# PC20230001.net
KiCad netlist of a schematic drawn in EasyEDA Pro
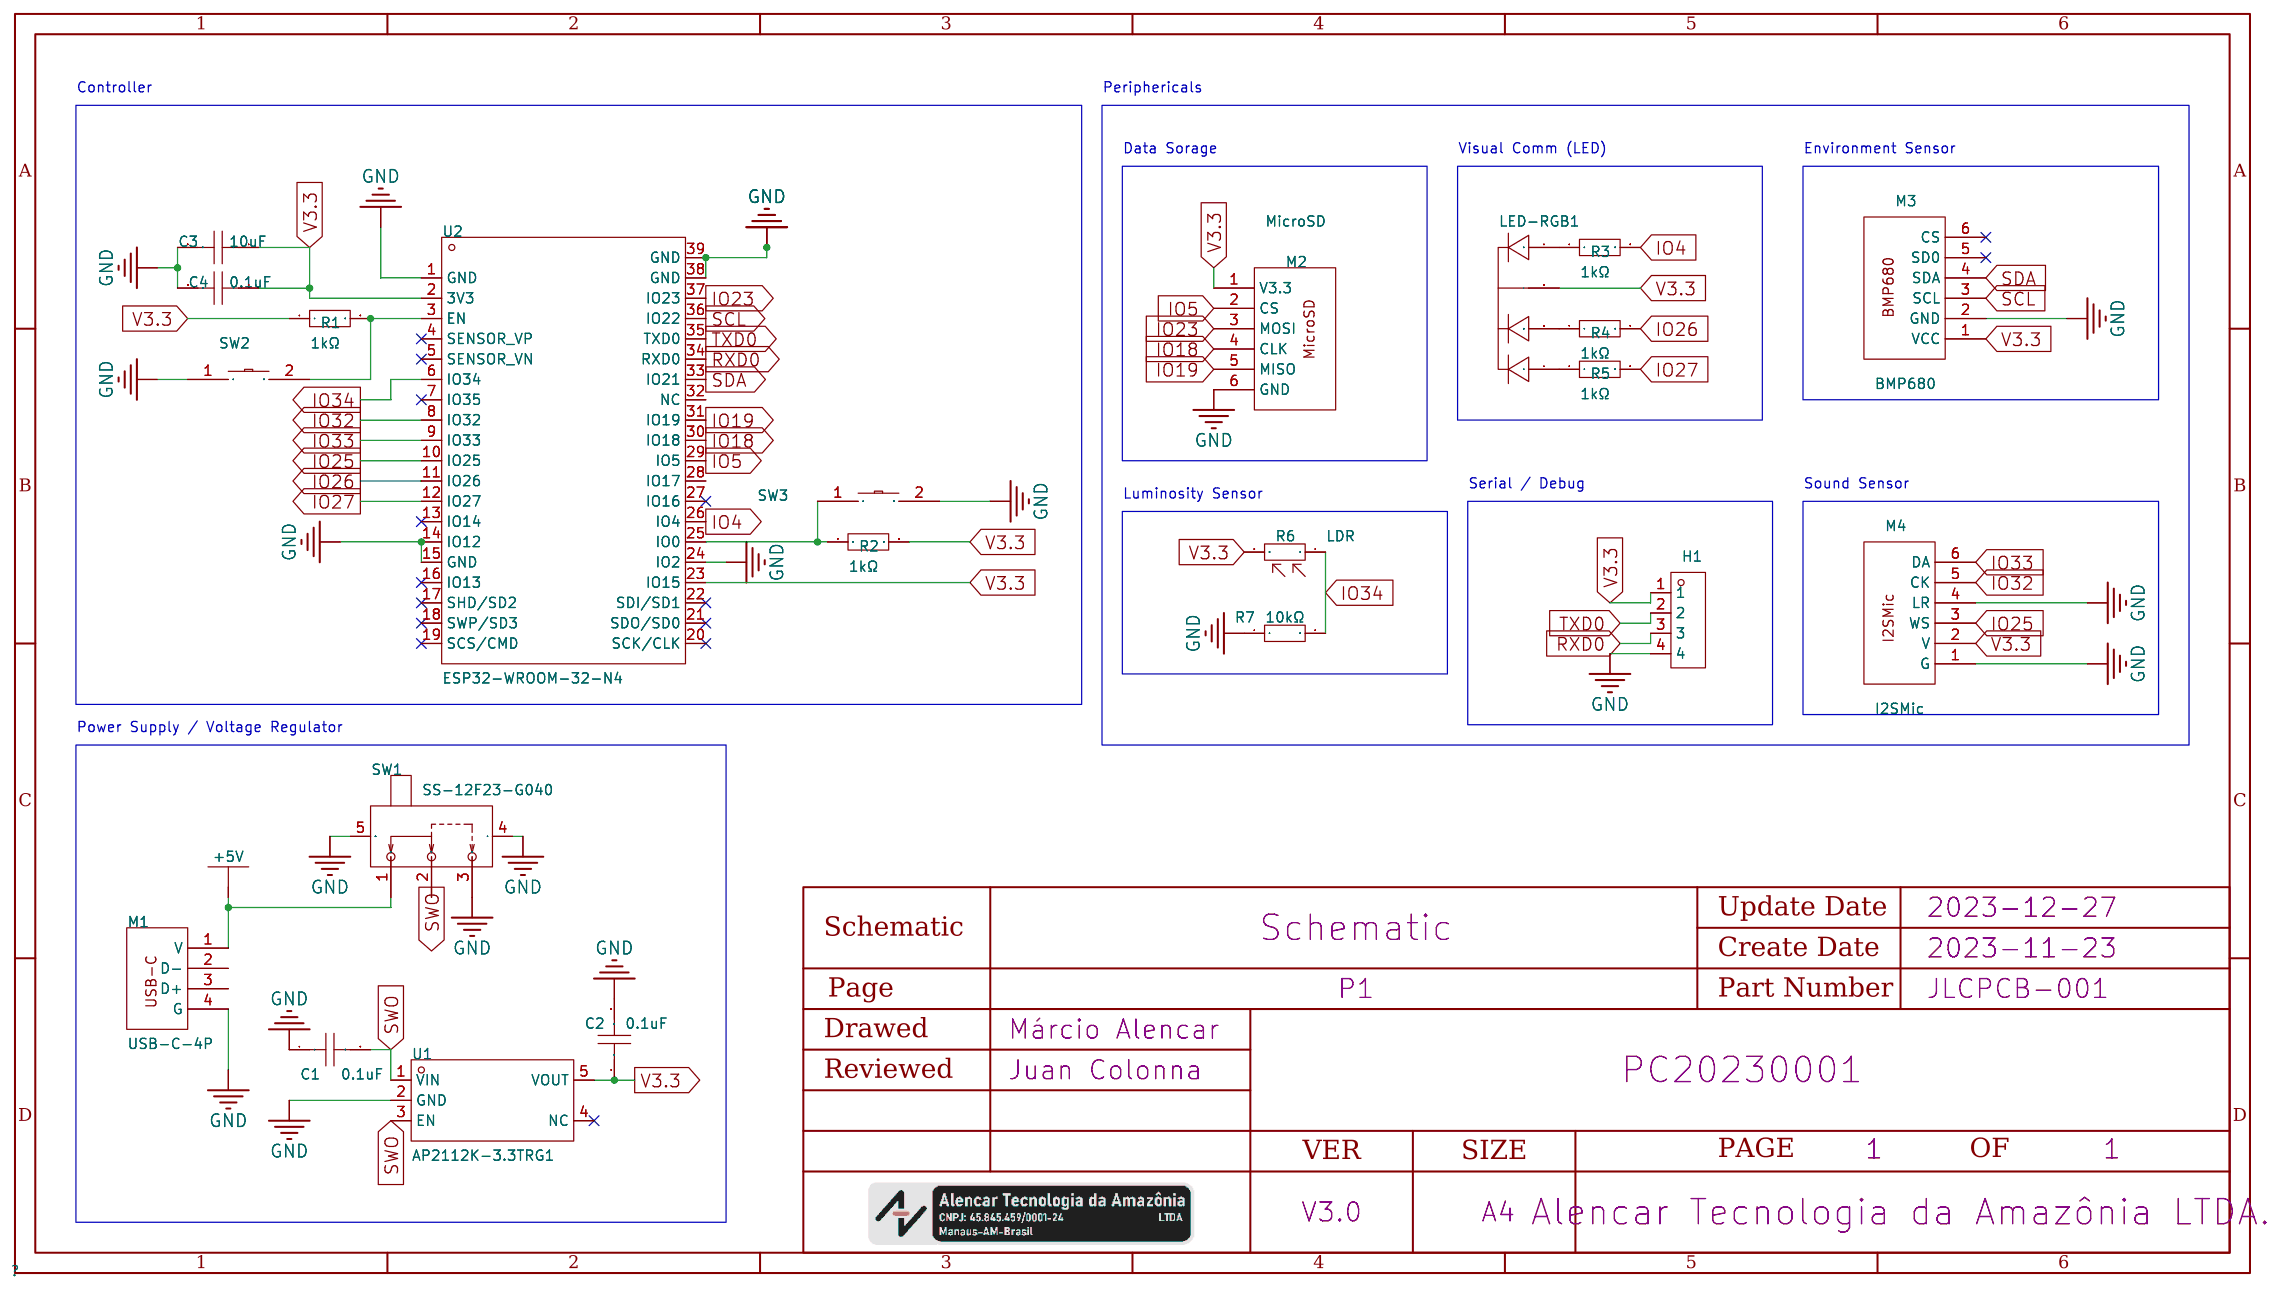
[diagram p0: schematic sheet]

(export (version "E")
  (design (tool "Eeschema 10.0.6"))
  (components
    (comp (ref "C1")
      (value "0.1uF")
      (footprint "easyedapro:C0201")
      (libsource (lib "easyedapro") (part "CAP"))
    )
    (comp (ref "C2")
      (value "0.1uF")
      (footprint "easyedapro:C0201")
      (libsource (lib "easyedapro") (part "CAP"))
    )
    (comp (ref "C3")
      (value "10uF")
      (footprint "easyedapro:C0201")
      (libsource (lib "easyedapro") (part "CAP"))
    )
    (comp (ref "C4")
      (value "0.1uF")
      (footprint "easyedapro:C0201")
      (libsource (lib "easyedapro") (part "CAP"))
    )
    (comp (ref "H1")
      (value "~")
      (footprint "easyedapro:HDR-TH_4P-P2.54-V-F")
      (libsource (lib "easyedapro") (part "2.54-1*4P母"))
    )
    (comp (ref "LED-RGB1")
      (value "LED-RGB 共阴 插件 直径5mm")
      (footprint "easyedapro:LED-TH_4P-BD5.8-P1.30")
      (libsource (lib "easyedapro") (part "LED-RGB 共阴 插件 直径5MM"))
    )
    (comp (ref "M1")
      (value "USB-C-4P")
      (footprint "easyedapro:USB-C-4P_SMD")
      (libsource (lib "easyedapro") (part "USB-C"))
    )
    (comp (ref "M2")
      (value "MicroSD")
      (footprint "easyedapro:MicroSD_SMD")
      (libsource (lib "easyedapro") (part "MicroSD"))
    )
    (comp (ref "M3")
      (value "BMP680")
      (footprint "easyedapro:BMP680_SMD")
      (libsource (lib "easyedapro") (part "BMP680"))
    )
    (comp (ref "M4")
      (value "I2SMic")
      (footprint "easyedapro:I2SMic_SMD")
      (libsource (lib "easyedapro") (part "I2SMicrophone"))
    )
    (comp (ref "R1")
      (value "1kΩ")
      (footprint "easyedapro:R_AXIAL-0.4")
      (libsource (lib "easyedapro") (part "Res"))
    )
    (comp (ref "R2")
      (value "1kΩ")
      (footprint "easyedapro:R_AXIAL-0.4")
      (libsource (lib "easyedapro") (part "Res"))
    )
    (comp (ref "R3")
      (value "1kΩ")
      (footprint "easyedapro:R_AXIAL-0.4")
      (libsource (lib "easyedapro") (part "Res"))
    )
    (comp (ref "R4")
      (value "1kΩ")
      (footprint "easyedapro:R_AXIAL-0.4")
      (libsource (lib "easyedapro") (part "Res"))
    )
    (comp (ref "R5")
      (value "1kΩ")
      (footprint "easyedapro:R_AXIAL-0.4")
      (libsource (lib "easyedapro") (part "Res"))
    )
    (comp (ref "R6")
      (value "LDR")
      (footprint "easyedapro:RES-TH_L7.0-W5.9-P5.00-D0.5")
      (fields (field (name "Manufacturer") "JCHL(晶创和立)"))
      (libsource (lib "easyedapro") (part "GL7549"))
    )
    (comp (ref "R7")
      (value "10kΩ")
      (footprint "easyedapro:R_AXIAL-0.4")
      (libsource (lib "easyedapro") (part "Res"))
    )
    (comp (ref "SW1")
      (value "SS-12F23-G040")
      (footprint "easyedapro:SW-TH_SS-12F23-G040")
      (fields (field (name "Manufacturer") "G-Switch(品赞)"))
      (libsource (lib "easyedapro") (part "SS-12F23-G040"))
    )
    (comp (ref "SW2")
      (value "TS-1101-C-W")
      (footprint "easyedapro:SW-SMD_L6.0-W3.3-LS8.0")
      (fields (field (name "Manufacturer") "XKB Connectivity(中国星坤)"))
      (libsource (lib "easyedapro") (part "TS-1101-C-W"))
    )
    (comp (ref "SW3")
      (value "TS-1101-C-W")
      (footprint "easyedapro:SW-SMD_L6.0-W3.3-LS8.0")
      (fields (field (name "Manufacturer") "XKB Connectivity(中国星坤)"))
      (libsource (lib "easyedapro") (part "TS-1101-C-W"))
    )
    (comp (ref "U1")
      (value "AP2112K-3.3TRG1")
      (footprint "easyedapro:SOT-25-5_L2.9-W1.6-P0.95-LS2.8-BL")
      (fields (field (name "Manufacturer") "DIODES(美台)"))
      (libsource (lib "easyedapro") (part "AP2112K-3.3TRG1"))
    )
    (comp (ref "U2")
      (value "ESP32-WROOM-32-N4")
      (footprint "easyedapro:WIFIM-SMD_ESP32-WROOM-32-N4")
      (fields (field (name "Manufacturer") "ESPRESSIF(乐鑫)"))
      (libsource (lib "easyedapro") (part "ESP32-WROOM-32"))
    )
  )
  (nets
    (net (code "1") (name "+5V") (class "Default")
      (node (ref "M1") (pin "1") (pinfunction "V_1") (pintype "input"))
      (node (ref "SW1") (pin "1") (pinfunction "1_1") (pintype "input"))
    )
    (net (code "2") (name "GND") (class "Default")
      (node (ref "C1") (pin "1") (pinfunction "1_1") (pintype "input"))
      (node (ref "C2") (pin "2") (pinfunction "2_2") (pintype "input"))
      (node (ref "C3") (pin "2") (pinfunction "2_2") (pintype "input"))
      (node (ref "C4") (pin "2") (pinfunction "2_2") (pintype "input"))
      (node (ref "H1") (pin "4") (pinfunction "4_4") (pintype "input"))
      (node (ref "M1") (pin "4") (pinfunction "G_4") (pintype "input"))
      (node (ref "M2") (pin "6") (pinfunction "GND_6") (pintype "input"))
      (node (ref "M3") (pin "2") (pinfunction "GND_2") (pintype "input"))
      (node (ref "M4") (pin "1") (pinfunction "G_1") (pintype "input"))
      (node (ref "M4") (pin "4") (pinfunction "LR_4") (pintype "input"))
      (node (ref "R7") (pin "1") (pinfunction "1_1") (pintype "input"))
      (node (ref "SW1") (pin "3") (pinfunction "3_3") (pintype "input"))
      (node (ref "SW1") (pin "4") (pinfunction "4_4") (pintype "input"))
      (node (ref "SW1") (pin "5") (pinfunction "5_5") (pintype "input"))
      (node (ref "SW2") (pin "1") (pinfunction "1_1") (pintype "input"))
      (node (ref "SW3") (pin "2") (pinfunction "2_2") (pintype "input"))
      (node (ref "U1") (pin "2") (pinfunction "GND_2") (pintype "input"))
      (node (ref "U2") (pin "1") (pinfunction "GND_1") (pintype "input"))
      (node (ref "U2") (pin "14") (pinfunction "IO12_14") (pintype "input"))
      (node (ref "U2") (pin "15") (pinfunction "GND_15") (pintype "input"))
      (node (ref "U2") (pin "24") (pinfunction "IO2_24") (pintype "input"))
      (node (ref "U2") (pin "38") (pinfunction "GND_38") (pintype "input"))
      (node (ref "U2") (pin "39") (pinfunction "GND_39") (pintype "input"))
    )
    (net (code "3") (name "IO4") (class "Default")
      (node (ref "R3") (pin "2") (pinfunction "2_2") (pintype "input"))
      (node (ref "U2") (pin "26") (pinfunction "IO4_26") (pintype "input"))
    )
    (net (code "4") (name "IO5") (class "Default")
      (node (ref "M2") (pin "2") (pinfunction "CS_2") (pintype "input"))
      (node (ref "U2") (pin "29") (pinfunction "IO5_29") (pintype "input"))
    )
    (net (code "5") (name "IO18") (class "Default")
      (node (ref "M2") (pin "4") (pinfunction "CLK_4") (pintype "input"))
      (node (ref "U2") (pin "30") (pinfunction "IO18_30") (pintype "input"))
    )
    (net (code "6") (name "IO19") (class "Default")
      (node (ref "M2") (pin "5") (pinfunction "MISO_5") (pintype "input"))
      (node (ref "U2") (pin "31") (pinfunction "IO19_31") (pintype "input"))
    )
    (net (code "7") (name "IO23") (class "Default")
      (node (ref "M2") (pin "3") (pinfunction "MOSI_3") (pintype "input"))
      (node (ref "U2") (pin "37") (pinfunction "IO23_37") (pintype "input"))
    )
    (net (code "8") (name "IO25") (class "Default")
      (node (ref "M4") (pin "3") (pinfunction "WS_3") (pintype "input"))
      (node (ref "U2") (pin "10") (pinfunction "IO25_10") (pintype "input"))
    )
    (net (code "9") (name "IO26") (class "Default")
      (node (ref "R4") (pin "2") (pinfunction "2_2") (pintype "input"))
      (node (ref "U2") (pin "11") (pinfunction "IO26_11") (pintype "input"))
    )
    (net (code "10") (name "IO27") (class "Default")
      (node (ref "R5") (pin "2") (pinfunction "2_2") (pintype "input"))
      (node (ref "U2") (pin "12") (pinfunction "IO27_12") (pintype "input"))
    )
    (net (code "11") (name "IO32") (class "Default")
      (node (ref "M4") (pin "5") (pinfunction "CK_5") (pintype "input"))
      (node (ref "U2") (pin "8") (pinfunction "IO32_8") (pintype "input"))
    )
    (net (code "12") (name "IO33") (class "Default")
      (node (ref "M4") (pin "6") (pinfunction "DA_6") (pintype "input"))
      (node (ref "U2") (pin "9") (pinfunction "IO33_9") (pintype "input"))
    )
    (net (code "13") (name "IO34") (class "Default")
      (node (ref "R6") (pin "1") (pinfunction "1_1") (pintype "input"))
      (node (ref "R7") (pin "2") (pinfunction "2_2") (pintype "input"))
      (node (ref "U2") (pin "6") (pinfunction "IO34_6") (pintype "input"))
    )
    (net (code "14") (name "Net-(LED-RGB1-Pad1)") (class "Default")
      (node (ref "LED-RGB1") (pin "1") (pinfunction "1_1") (pintype "input"))
      (node (ref "R3") (pin "1") (pinfunction "1_1") (pintype "input"))
    )
    (net (code "15") (name "Net-(LED-RGB1-Pad3)") (class "Default")
      (node (ref "LED-RGB1") (pin "3") (pinfunction "3_3") (pintype "input"))
      (node (ref "R4") (pin "1") (pinfunction "1_1") (pintype "input"))
    )
    (net (code "16") (name "Net-(LED-RGB1-Pad4)") (class "Default")
      (node (ref "LED-RGB1") (pin "4") (pinfunction "4_4") (pintype "input"))
      (node (ref "R5") (pin "1") (pinfunction "1_1") (pintype "input"))
    )
    (net (code "17") (name "Net-(U2-EN)") (class "Default")
      (node (ref "R1") (pin "2") (pinfunction "2_2") (pintype "input"))
      (node (ref "SW2") (pin "2") (pinfunction "2_2") (pintype "input"))
      (node (ref "U2") (pin "3") (pinfunction "EN_3") (pintype "input"))
    )
    (net (code "18") (name "Net-(U2-IO0)") (class "Default")
      (node (ref "R2") (pin "1") (pinfunction "1_1") (pintype "input"))
      (node (ref "SW3") (pin "1") (pinfunction "1_1") (pintype "input"))
      (node (ref "U2") (pin "25") (pinfunction "IO0_25") (pintype "input"))
    )
    (net (code "19") (name "RXD0") (class "Default")
      (node (ref "H1") (pin "3") (pinfunction "3_3") (pintype "input"))
      (node (ref "U2") (pin "34") (pinfunction "RXD0_34") (pintype "input"))
    )
    (net (code "20") (name "SCL") (class "Default")
      (node (ref "M3") (pin "3") (pinfunction "SCL_3") (pintype "input"))
      (node (ref "U2") (pin "36") (pinfunction "IO22_36") (pintype "input"))
    )
    (net (code "21") (name "SDA") (class "Default")
      (node (ref "M3") (pin "4") (pinfunction "SDA_4") (pintype "input"))
      (node (ref "U2") (pin "33") (pinfunction "IO21_33") (pintype "input"))
    )
    (net (code "22") (name "SWO") (class "Default")
      (node (ref "C1") (pin "2") (pinfunction "2_2") (pintype "input"))
      (node (ref "SW1") (pin "2") (pinfunction "2_2") (pintype "input"))
      (node (ref "U1") (pin "1") (pinfunction "VIN_1") (pintype "input"))
      (node (ref "U1") (pin "3") (pinfunction "EN_3") (pintype "input"))
    )
    (net (code "23") (name "TXD0") (class "Default")
      (node (ref "H1") (pin "2") (pinfunction "2_2") (pintype "input"))
      (node (ref "U2") (pin "35") (pinfunction "TXD0_35") (pintype "input"))
    )
    (net (code "24") (name "V3.3") (class "Default")
      (node (ref "C2") (pin "1") (pinfunction "1_1") (pintype "input"))
      (node (ref "C3") (pin "1") (pinfunction "1_1") (pintype "input"))
      (node (ref "C4") (pin "1") (pinfunction "1_1") (pintype "input"))
      (node (ref "H1") (pin "1") (pinfunction "1_1") (pintype "input"))
      (node (ref "LED-RGB1") (pin "2") (pinfunction "-_2") (pintype "input"))
      (node (ref "M2") (pin "1") (pinfunction "V3.3_1") (pintype "input"))
      (node (ref "M3") (pin "1") (pinfunction "VCC_1") (pintype "input"))
      (node (ref "M4") (pin "2") (pinfunction "V_2") (pintype "input"))
      (node (ref "R1") (pin "1") (pinfunction "1_1") (pintype "input"))
      (node (ref "R2") (pin "2") (pinfunction "2_2") (pintype "input"))
      (node (ref "R6") (pin "2") (pinfunction "2_2") (pintype "input"))
      (node (ref "U1") (pin "5") (pinfunction "VOUT_5") (pintype "input"))
      (node (ref "U2") (pin "2") (pinfunction "3V3_2") (pintype "input"))
      (node (ref "U2") (pin "23") (pinfunction "IO15_23") (pintype "input"))
    )
    (net (code "25") (name "unconnected-(M1-D+-Pad3)") (class "Default")
      (node (ref "M1") (pin "3") (pinfunction "D+_3") (pintype "input"))
    )
    (net (code "26") (name "unconnected-(M1-D--Pad2)") (class "Default")
      (node (ref "M1") (pin "2") (pinfunction "D-_2") (pintype "input"))
    )
    (net (code "27") (name "unconnected-(M3-CS-Pad6)") (class "Default")
      (node (ref "M3") (pin "6") (pinfunction "CS_6") (pintype "input+no_connect"))
    )
    (net (code "28") (name "unconnected-(M3-SD0-Pad5)") (class "Default")
      (node (ref "M3") (pin "5") (pinfunction "SD0_5") (pintype "input+no_connect"))
    )
    (net (code "29") (name "unconnected-(U1-NC-Pad4)") (class "Default")
      (node (ref "U1") (pin "4") (pinfunction "NC_4") (pintype "input+no_connect"))
    )
    (net (code "30") (name "unconnected-(U2-IO13-Pad16)") (class "Default")
      (node (ref "U2") (pin "16") (pinfunction "IO13_16") (pintype "input+no_connect"))
    )
    (net (code "31") (name "unconnected-(U2-IO14-Pad13)") (class "Default")
      (node (ref "U2") (pin "13") (pinfunction "IO14_13") (pintype "input+no_connect"))
    )
    (net (code "32") (name "unconnected-(U2-IO16-Pad27)") (class "Default")
      (node (ref "U2") (pin "27") (pinfunction "IO16_27") (pintype "input+no_connect"))
    )
    (net (code "33") (name "unconnected-(U2-IO17-Pad28)") (class "Default")
      (node (ref "U2") (pin "28") (pinfunction "IO17_28") (pintype "input"))
    )
    (net (code "34") (name "unconnected-(U2-IO35-Pad7)") (class "Default")
      (node (ref "U2") (pin "7") (pinfunction "IO35_7") (pintype "input+no_connect"))
    )
    (net (code "35") (name "unconnected-(U2-NC-Pad32)") (class "Default")
      (node (ref "U2") (pin "32") (pinfunction "NC_32") (pintype "input"))
    )
    (net (code "36") (name "unconnected-(U2-SCK{slash}CLK-Pad20)") (class "Default")
      (node (ref "U2") (pin "20") (pinfunction "SCK/CLK_20") (pintype "input+no_connect"))
    )
    (net (code "37") (name "unconnected-(U2-SCS{slash}CMD-Pad19)") (class "Default")
      (node (ref "U2") (pin "19") (pinfunction "SCS/CMD_19") (pintype "input+no_connect"))
    )
    (net (code "38") (name "unconnected-(U2-SDI{slash}SD1-Pad22)") (class "Default")
      (node (ref "U2") (pin "22") (pinfunction "SDI/SD1_22") (pintype "input+no_connect"))
    )
    (net (code "39") (name "unconnected-(U2-SDO{slash}SD0-Pad21)") (class "Default")
      (node (ref "U2") (pin "21") (pinfunction "SDO/SD0_21") (pintype "input+no_connect"))
    )
    (net (code "40") (name "unconnected-(U2-SENSOR_VN-Pad5)") (class "Default")
      (node (ref "U2") (pin "5") (pinfunction "SENSOR_VN_5") (pintype "input+no_connect"))
    )
    (net (code "41") (name "unconnected-(U2-SENSOR_VP-Pad4)") (class "Default")
      (node (ref "U2") (pin "4") (pinfunction "SENSOR_VP_4") (pintype "input+no_connect"))
    )
    (net (code "42") (name "unconnected-(U2-SHD{slash}SD2-Pad17)") (class "Default")
      (node (ref "U2") (pin "17") (pinfunction "SHD/SD2_17") (pintype "input+no_connect"))
    )
    (net (code "43") (name "unconnected-(U2-SWP{slash}SD3-Pad18)") (class "Default")
      (node (ref "U2") (pin "18") (pinfunction "SWP/SD3_18") (pintype "input+no_connect"))
    )
  )
)
